# PowerBoard.net
KiCad netlist of a schematic drawn in Altium Designer
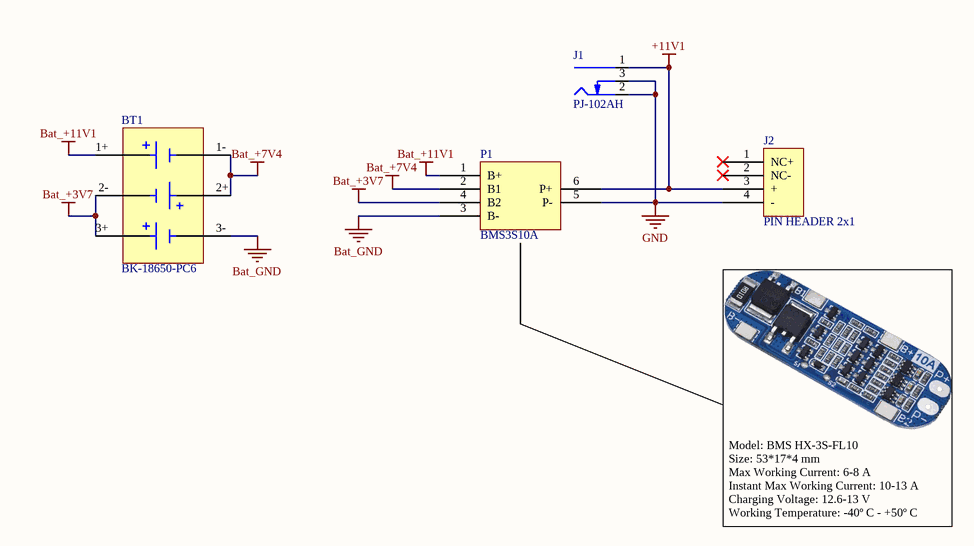
[diagram p0: PowerBoard.SchDoc]

(export (version "E")
  (design (tool "Eeschema 10.0.6"))
  (components
    (comp (ref "BT1")
      (value "BK-18650-PC6")
      (footprint "BottomBoardLib:BAT_BK-18650-PC6")
      (description "Battery Holder _Open_ 18650 3 Cell PC Pin")
      (fields (field (name "MF") "MPD"))
      (libsource (lib "BottomBoardLib") (part "BK-18650-PC6"))
    )
    (comp (ref "J1")
      (value "PJ-102AH")
      (footprint "CUI PJ-102AH")
      (description "CONN PWR JACK 2X5.5MM SOLDER")
      (fields (field (name "MANUFACTURER") "CUI Devices"))
      (libsource (lib "BottomBoardLib") (part "PJ-102AH"))
    )
    (comp (ref "J2")
      (value "PIN HEADER 2x1")
      (footprint "ControlBoard:M20-9950245")
      (description "M20-9950245 Pin Connector")
      (libsource (lib "ControlBoard") (part "M20-9950245"))
    )
    (comp (ref "P1") (value "BMS3S10A") (footprint "BMS") (libsource (lib "Robot") (part "BMS")))
  )
  (nets
    (net (code "1") (name "+11V1") (class "Default")
      (node (ref "J1") (pin "1") (pinfunction "Centre_1") (pintype "passive"))
      (node (ref "J2") (pin "3") (pinfunction "+_3") (pintype "power_in"))
      (node (ref "P1") (pin "6") (pinfunction "P+_6") (pintype "passive"))
    )
    (net (code "2") (name "Bat_+3V7") (class "Default")
      (node (ref "BT1") (pin "2-") (pinfunction "2-_2-") (pintype "passive"))
      (node (ref "BT1") (pin "3+") (pinfunction "3+_3+") (pintype "passive"))
      (node (ref "P1") (pin "4") (pinfunction "B2_4") (pintype "passive"))
    )
    (net (code "3") (name "Bat_+7V4") (class "Default")
      (node (ref "BT1") (pin "1-") (pinfunction "1-_1-") (pintype "passive"))
      (node (ref "BT1") (pin "2+") (pinfunction "2+_2+") (pintype "passive"))
      (node (ref "P1") (pin "2") (pinfunction "B1_2") (pintype "passive"))
    )
    (net (code "4") (name "Bat_+11V1") (class "Default")
      (node (ref "BT1") (pin "1+") (pinfunction "1+_1+") (pintype "passive"))
      (node (ref "P1") (pin "1") (pinfunction "B+_1") (pintype "passive"))
    )
    (net (code "5") (name "Bat_GND") (class "Default")
      (node (ref "BT1") (pin "3-") (pinfunction "3-_3-") (pintype "passive"))
      (node (ref "P1") (pin "3") (pinfunction "B-_3") (pintype "passive"))
    )
    (net (code "6") (name "GND") (class "Default")
      (node (ref "J1") (pin "2") (pinfunction "Outer_2") (pintype "passive"))
      (node (ref "J1") (pin "3") (pinfunction "SW_3") (pintype "passive"))
      (node (ref "J2") (pin "4") (pinfunction "-_4") (pintype "power_in"))
      (node (ref "P1") (pin "5") (pinfunction "P-_5") (pintype "passive"))
    )
    (net (code "7") (name "unconnected-(J2-NC+-Pad1)") (class "Default")
      (node (ref "J2") (pin "1") (pinfunction "NC+_1") (pintype "power_in+no_connect"))
    )
    (net (code "8") (name "unconnected-(J2-NC--Pad2)") (class "Default")
      (node (ref "J2") (pin "2") (pinfunction "NC-_2") (pintype "power_in+no_connect"))
    )
  )
)
